# STM32F303RET6.net
KiCad netlist of a schematic drawn in Altium Designer
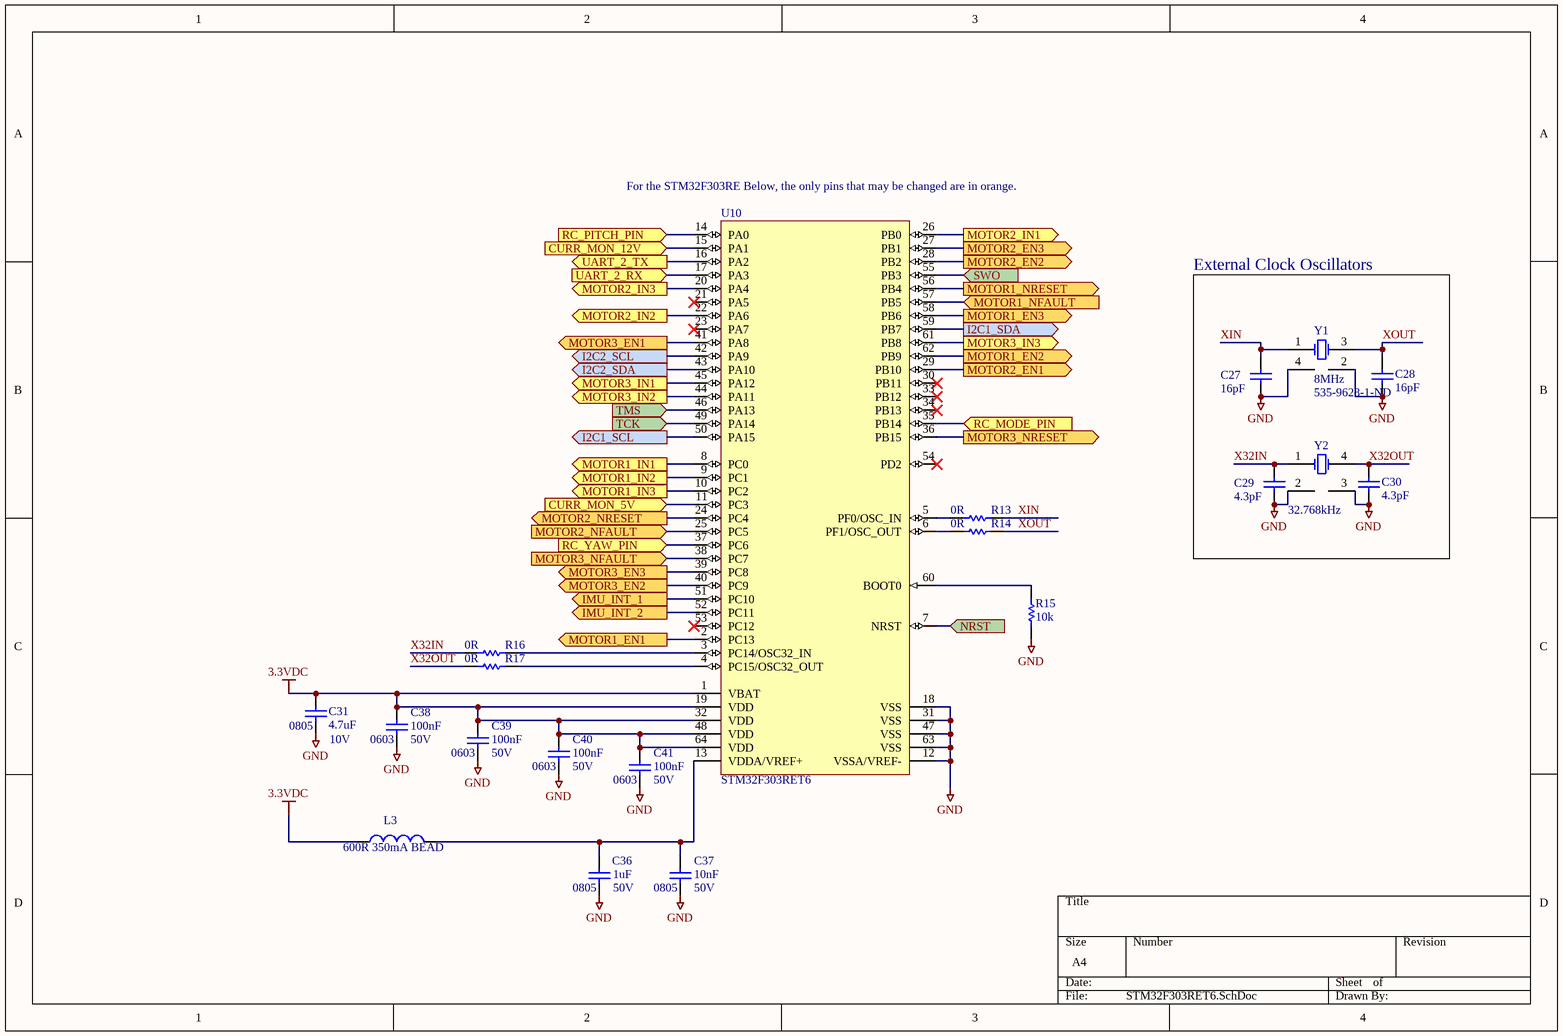
[diagram p0: STM32F303RET6.SchDoc]

(export (version "E")
  (design (tool "Eeschema 10.0.6"))
  (components
    (comp (ref "C27")
      (value "16pF")
      (footprint "CAPC1608N(0603\")")
      (description "Capacitor, Ceramic, 50V, +/- 5%, 0603, SMD, C0G/NP0")
      (fields
        (field (name "MFG") "Samsung Electro-Mechanics America, Inc")
        (field (name "VOLTAGE") "50V")
        (field (name "PUBLISHER") "UVic AERO, Luke Mills")
      )
      (libsource (lib "AERO Integrated Library - Capacitors") (part "16pF, 50V, 0603, SMD, Ceramic"))
    )
    (comp (ref "C28")
      (value "16pF")
      (footprint "CAPC1608N(0603\")")
      (description "Capacitor, Ceramic, 50V, +/- 5%, 0603, SMD, C0G/NP0")
      (fields
        (field (name "MFG") "Samsung Electro-Mechanics America, Inc")
        (field (name "VOLTAGE") "50V")
        (field (name "PUBLISHER") "UVic AERO, Luke Mills")
      )
      (libsource (lib "AERO Integrated Library - Capacitors") (part "16pF, 50V, 0603, SMD, Ceramic"))
    )
    (comp (ref "C29")
      (value "4.3pF")
      (footprint "CAPC1608N(0603\")")
      (description "Capacitor, Ceramic, 50V, +/- 0.1pF, 0603 SMD, C0G, NP0")
      (fields
        (field (name "MFG") "Samsung Electro-Mechanics")
        (field (name "PUBLISHER") "UVic AERO, Taylor Long")
      )
      (libsource (lib "AERO Integrated Library - Capacitors") (part "4.3pF 50V 0603 SMD, Ceramic"))
    )
    (comp (ref "C30")
      (value "4.3pF")
      (footprint "CAPC1608N(0603\")")
      (description "Capacitor, Ceramic, 50V, +/- 0.1pF, 0603 SMD, C0G, NP0")
      (fields
        (field (name "MFG") "Samsung Electro-Mechanics")
        (field (name "PUBLISHER") "UVic AERO, Taylor Long")
      )
      (libsource (lib "AERO Integrated Library - Capacitors") (part "4.3pF 50V 0603 SMD, Ceramic"))
    )
    (comp (ref "C31")
      (value "4.7uF")
      (footprint "CAPC2012N(0805\")")
      (description "CAP CER 4.7UF 10V, +/- 10%, 0805 SMD, X7R")
      (fields
        (field (name "MANUFACTURER") "KEMET")
        (field (name "MANUFACTURER PART NUMBER") "C0805C475K8PACTU")
        (field (name "CASE/PACKAGE") "0805")
        (field (name "VOLTAGE RATING (DC)") "10V")
        (field (name "PUBLISHER") "TRAXX Automation Ltd.")
      )
      (libsource (lib "BLDC_Gimbal_Lib") (part "C0805C475K8PACTU"))
    )
    (comp (ref "C36")
      (value "CL21A105KBCLNNC")
      (footprint "CAPC2012N(0805\")")
      (description "CAP CER 1uF 50V X5R 10% SMD 0805 85C Cardboard T/R")
      (fields
        (field (name "MANUFACTURER") "Samsung")
        (field (name "TOLERANCE") "10%")
        (field (name "VOLTAGE RATING") "50V")
        (field (name "CASE/PACKAGE") "0805")
        (field (name "CAPACITANCE") "1uF")
      )
      (libsource (lib "BLDC_Gimbal_Lib") (part "CL21A105KBCLNNC"))
    )
    (comp (ref "C37")
      (value "10nF")
      (footprint "CAPC2012N(0805\")")
      (description "CAP CER 10nF 50V, +/- 10%, 0805 SMD, X7R C0805C103K5RACTU")
      (fields
        (field (name "MANUFACTURER") "KEMET")
        (field (name "MANUFACTURER PART NUMBER") "C0805C103K5RACTU")
        (field (name "CASE/PACKAGE") "0805")
        (field (name "VOLTAGE RATING") "50V")
        (field (name "PUBLISHER") "UVic AERO")
      )
      (libsource (lib "BLDC_Gimbal_Lib") (part "C0805C103K5RACTU"))
    )
    (comp (ref "C38")
      (value "100nF")
      (footprint "CAPC1608N(0603\")")
      (description "CAP CER 0.1UF 50V X7R 0603")
      (fields
        (field (name "MANUFACTURER") "Samsung")
        (field (name "MANUFACTURER PART NUMBER") "CL10B104KB8SFNC")
        (field (name "CASE CODE (IMPERIAL)") "0603")
        (field (name "VOLTAGE RATING") "50V")
      )
      (libsource (lib "BLDC_Gimbal_Lib") (part "CL10B104KB8SFNC"))
    )
    (comp (ref "C39")
      (value "100nF")
      (footprint "CAPC1608N(0603\")")
      (description "CAP CER 0.1UF 50V X7R 0603")
      (fields
        (field (name "MANUFACTURER") "Samsung")
        (field (name "MANUFACTURER PART NUMBER") "CL10B104KB8SFNC")
        (field (name "CASE CODE (IMPERIAL)") "0603")
        (field (name "VOLTAGE RATING") "50V")
      )
      (libsource (lib "BLDC_Gimbal_Lib") (part "CL10B104KB8SFNC"))
    )
    (comp (ref "C40")
      (value "100nF")
      (footprint "CAPC1608N(0603\")")
      (description "CAP CER 0.1UF 50V X7R 0603")
      (fields
        (field (name "MANUFACTURER") "Samsung")
        (field (name "MANUFACTURER PART NUMBER") "CL10B104KB8SFNC")
        (field (name "CASE CODE (IMPERIAL)") "0603")
        (field (name "VOLTAGE RATING") "50V")
      )
      (libsource (lib "BLDC_Gimbal_Lib") (part "CL10B104KB8SFNC"))
    )
    (comp (ref "C41")
      (value "100nF")
      (footprint "CAPC1608N(0603\")")
      (description "CAP CER 0.1UF 50V X7R 0603")
      (fields
        (field (name "MANUFACTURER") "Samsung")
        (field (name "MANUFACTURER PART NUMBER") "CL10B104KB8SFNC")
        (field (name "CASE CODE (IMPERIAL)") "0603")
        (field (name "VOLTAGE RATING") "50V")
      )
      (libsource (lib "BLDC_Gimbal_Lib") (part "CL10B104KB8SFNC"))
    )
    (comp (ref "L3")
      (value "600R 350mA BEAD")
      (footprint "RESC1608N(0603\")")
      (description "FERRITE BEAD 600 OHM 0603 1LN")
      (fields
        (field (name "MANUFACTURER") "Taiyo Yuden")
        (field (name "MANUFACTURER PART NUMBER") "BK1608HS601-T")
      )
      (libsource (lib "BLDC_Gimbal_Lib") (part "BK1608HS601-T"))
    )
    (comp (ref "R13")
      (value "0R")
      (footprint "RESC1608N(0603\")")
      (description "Resistor, 0R, 1/10 W, 0603 SMD, 0R, +/-200ppm/C, Thick Film")
      (fields (field (name "POWER") "1/10W") (field (name "PUBLISHER") "TRAXX Automation Ltd."))
      (libsource (lib "BLDC_Gimbal_Lib") (part "0R, 1/10 W, 0603 SMD"))
    )
    (comp (ref "R14")
      (value "0R")
      (footprint "RESC1608N(0603\")")
      (description "Resistor, 0R, 1/10 W, 0603 SMD, 0R, +/-200ppm/C, Thick Film")
      (fields (field (name "POWER") "1/10W") (field (name "PUBLISHER") "TRAXX Automation Ltd."))
      (libsource (lib "BLDC_Gimbal_Lib") (part "0R, 1/10 W, 0603 SMD"))
    )
    (comp (ref "R15")
      (value "CRCW080510K0FKEA")
      (footprint "RESC2012N(0805\")")
      (description "RES SMD 10K OHM 1% 1/8W 0805")
      (fields
        (field (name "MANUFACTURER") "Vishay")
        (field (name "TOLERANCE") "1%")
        (field (name "RESISTANCE") "10k")
      )
      (libsource (lib "BLDC_Gimbal_Lib") (part "CRCW080510K0FKEA"))
    )
    (comp (ref "R16")
      (value "0R")
      (footprint "RESC1608N(0603\")")
      (description "Resistor, 0R, 1/10 W, 0603 SMD, 0R, +/-200ppm/C, Thick Film")
      (fields (field (name "POWER") "1/10W") (field (name "PUBLISHER") "TRAXX Automation Ltd."))
      (libsource (lib "BLDC_Gimbal_Lib") (part "0R, 1/10 W, 0603 SMD"))
    )
    (comp (ref "R17")
      (value "0R")
      (footprint "RESC1608N(0603\")")
      (description "Resistor, 0R, 1/10 W, 0603 SMD, 0R, +/-200ppm/C, Thick Film")
      (fields (field (name "POWER") "1/10W") (field (name "PUBLISHER") "TRAXX Automation Ltd."))
      (libsource (lib "BLDC_Gimbal_Lib") (part "0R, 1/10 W, 0603 SMD"))
    )
    (comp (ref "U10")
      (value "STM32F303RET6")
      (footprint "STM-LQFP64_M")
      (libsource (lib "BLDC_Gimbal_Lib") (part "CMP-0537-00048-1"))
    )
    (comp (ref "Y1")
      (value "8MHz")
      (footprint "CRYSTAL 4-SMD, 3.60x6.00mm")
      (description "Crystal Oscillator 8MHz, 18pF, 4-SMD")
      (fields
        (field (name "SUPPLIER PART NUMBER 1") "535-9628-1-ND")
        (field (name "PUBLISHER") "UVic AERO, Taylor Long")
      )
      (libsource (lib "AERO Schematic Library - Crystals & Oscillators") (part "Crystal 8MHz, 18pF, 4-SMD 6.0x3.6mm"))
    )
    (comp (ref "Y2")
      (value "32.768kHz")
      (footprint "SOJ550P380X260-4M")
      (description "Crystal Oscillator 32.768kHz, 4-SOJ 5.5mm")
      (fields (field (name "PUBLISHER") "UVic AERO. Taylor Long"))
      (libsource (lib "AERO Schematic Library - Crystals & Oscillators") (part "Crystal 32.768khz, 4-SOJ 5.5mm"))
    )
  )
  (nets
    (net (code "1") (name "/CURR_MON_5V") (class "Default")
      (node (ref "U10") (pin "11") (pinfunction "PC3_11") (pintype "bidirectional"))
    )
    (net (code "2") (name "/CURR_MON_12V") (class "Default")
      (node (ref "U10") (pin "15") (pinfunction "PA1_15") (pintype "bidirectional"))
    )
    (net (code "3") (name "/I2C1_SCL") (class "Default")
      (node (ref "U10") (pin "50") (pinfunction "PA15_50") (pintype "bidirectional"))
    )
    (net (code "4") (name "/I2C1_SDA") (class "Default")
      (node (ref "U10") (pin "59") (pinfunction "PB7_59") (pintype "bidirectional"))
    )
    (net (code "5") (name "/I2C2_SCL") (class "Default")
      (node (ref "U10") (pin "42") (pinfunction "PA9_42") (pintype "bidirectional"))
    )
    (net (code "6") (name "/I2C2_SDA") (class "Default")
      (node (ref "U10") (pin "43") (pinfunction "PA10_43") (pintype "bidirectional"))
    )
    (net (code "7") (name "/IMU_INT_1") (class "Default")
      (node (ref "U10") (pin "51") (pinfunction "PC10_51") (pintype "bidirectional"))
    )
    (net (code "8") (name "/IMU_INT_2") (class "Default")
      (node (ref "U10") (pin "52") (pinfunction "PC11_52") (pintype "bidirectional"))
    )
    (net (code "9") (name "/MOTOR1_EN1") (class "Default")
      (node (ref "U10") (pin "2") (pinfunction "PC13_2") (pintype "bidirectional"))
    )
    (net (code "10") (name "/MOTOR1_EN2") (class "Default")
      (node (ref "U10") (pin "62") (pinfunction "PB9_62") (pintype "bidirectional"))
    )
    (net (code "11") (name "/MOTOR1_EN3") (class "Default")
      (node (ref "U10") (pin "58") (pinfunction "PB6_58") (pintype "bidirectional"))
    )
    (net (code "12") (name "/MOTOR1_IN1") (class "Default")
      (node (ref "U10") (pin "8") (pinfunction "PC0_8") (pintype "bidirectional"))
    )
    (net (code "13") (name "/MOTOR1_IN2") (class "Default")
      (node (ref "U10") (pin "9") (pinfunction "PC1_9") (pintype "bidirectional"))
    )
    (net (code "14") (name "/MOTOR1_IN3") (class "Default")
      (node (ref "U10") (pin "10") (pinfunction "PC2_10") (pintype "bidirectional"))
    )
    (net (code "15") (name "/MOTOR1_NFAULT") (class "Default")
      (node (ref "U10") (pin "57") (pinfunction "PB5_57") (pintype "bidirectional"))
    )
    (net (code "16") (name "/MOTOR1_NRESET") (class "Default")
      (node (ref "U10") (pin "56") (pinfunction "PB4_56") (pintype "bidirectional"))
    )
    (net (code "17") (name "/MOTOR2_EN1") (class "Default")
      (node (ref "U10") (pin "29") (pinfunction "PB10_29") (pintype "bidirectional"))
    )
    (net (code "18") (name "/MOTOR2_EN2") (class "Default")
      (node (ref "U10") (pin "28") (pinfunction "PB2_28") (pintype "bidirectional"))
    )
    (net (code "19") (name "/MOTOR2_EN3") (class "Default")
      (node (ref "U10") (pin "27") (pinfunction "PB1_27") (pintype "bidirectional"))
    )
    (net (code "20") (name "/MOTOR2_IN1") (class "Default")
      (node (ref "U10") (pin "26") (pinfunction "PB0_26") (pintype "bidirectional"))
    )
    (net (code "21") (name "/MOTOR2_IN2") (class "Default")
      (node (ref "U10") (pin "22") (pinfunction "PA6_22") (pintype "bidirectional"))
    )
    (net (code "22") (name "/MOTOR2_IN3") (class "Default")
      (node (ref "U10") (pin "20") (pinfunction "PA4_20") (pintype "bidirectional"))
    )
    (net (code "23") (name "/MOTOR2_NFAULT") (class "Default")
      (node (ref "U10") (pin "25") (pinfunction "PC5_25") (pintype "bidirectional"))
    )
    (net (code "24") (name "/MOTOR2_NRESET") (class "Default")
      (node (ref "U10") (pin "24") (pinfunction "PC4_24") (pintype "bidirectional"))
    )
    (net (code "25") (name "/MOTOR3_EN1") (class "Default")
      (node (ref "U10") (pin "41") (pinfunction "PA8_41") (pintype "bidirectional"))
    )
    (net (code "26") (name "/MOTOR3_EN2") (class "Default")
      (node (ref "U10") (pin "40") (pinfunction "PC9_40") (pintype "bidirectional"))
    )
    (net (code "27") (name "/MOTOR3_EN3") (class "Default")
      (node (ref "U10") (pin "39") (pinfunction "PC8_39") (pintype "bidirectional"))
    )
    (net (code "28") (name "/MOTOR3_IN1") (class "Default")
      (node (ref "U10") (pin "45") (pinfunction "PA12_45") (pintype "bidirectional"))
    )
    (net (code "29") (name "/MOTOR3_IN2") (class "Default")
      (node (ref "U10") (pin "44") (pinfunction "PA11_44") (pintype "bidirectional"))
    )
    (net (code "30") (name "/MOTOR3_IN3") (class "Default")
      (node (ref "U10") (pin "61") (pinfunction "PB8_61") (pintype "bidirectional"))
    )
    (net (code "31") (name "/MOTOR3_NFAULT") (class "Default")
      (node (ref "U10") (pin "38") (pinfunction "PC7_38") (pintype "bidirectional"))
    )
    (net (code "32") (name "/MOTOR3_NRESET") (class "Default")
      (node (ref "U10") (pin "36") (pinfunction "PB15_36") (pintype "bidirectional"))
    )
    (net (code "33") (name "/NRST") (class "Default")
      (node (ref "U10") (pin "7") (pinfunction "NRST_7") (pintype "bidirectional"))
    )
    (net (code "34") (name "/RC_MODE_PIN") (class "Default")
      (node (ref "U10") (pin "35") (pinfunction "PB14_35") (pintype "bidirectional"))
    )
    (net (code "35") (name "/RC_PITCH_PIN") (class "Default")
      (node (ref "U10") (pin "14") (pinfunction "PA0_14") (pintype "bidirectional"))
    )
    (net (code "36") (name "/RC_YAW_PIN") (class "Default")
      (node (ref "U10") (pin "37") (pinfunction "PC6_37") (pintype "bidirectional"))
    )
    (net (code "37") (name "/SWO") (class "Default")
      (node (ref "U10") (pin "55") (pinfunction "PB3_55") (pintype "bidirectional"))
    )
    (net (code "38") (name "/TCK") (class "Default")
      (node (ref "U10") (pin "49") (pinfunction "PA14_49") (pintype "bidirectional"))
    )
    (net (code "39") (name "/TMS") (class "Default")
      (node (ref "U10") (pin "46") (pinfunction "PA13_46") (pintype "bidirectional"))
    )
    (net (code "40") (name "/UART_2_RX") (class "Default")
      (node (ref "U10") (pin "17") (pinfunction "PA3_17") (pintype "bidirectional"))
    )
    (net (code "41") (name "/UART_2_TX") (class "Default")
      (node (ref "U10") (pin "16") (pinfunction "PA2_16") (pintype "bidirectional"))
    )
    (net (code "42") (name "/X32IN") (class "Default")
      (node (ref "C29") (pin "2") (pinfunction "2_2") (pintype "passive"))
      (node (ref "R16") (pin "1") (pinfunction "1_1") (pintype "passive"))
      (node (ref "Y2") (pin "1") (pinfunction "OSC1_1") (pintype "passive"))
    )
    (net (code "43") (name "/X32OUT") (class "Default")
      (node (ref "C30") (pin "2") (pinfunction "2_2") (pintype "passive"))
      (node (ref "R17") (pin "1") (pinfunction "1_1") (pintype "passive"))
      (node (ref "Y2") (pin "4") (pinfunction "OSC2_4") (pintype "passive"))
    )
    (net (code "44") (name "/XIN") (class "Default")
      (node (ref "C27") (pin "2") (pinfunction "2_2") (pintype "passive"))
      (node (ref "R13") (pin "2") (pinfunction "2_2") (pintype "passive"))
      (node (ref "Y1") (pin "1") (pinfunction "OSC1_1") (pintype "passive"))
    )
    (net (code "45") (name "/XOUT") (class "Default")
      (node (ref "C28") (pin "2") (pinfunction "2_2") (pintype "passive"))
      (node (ref "R14") (pin "2") (pinfunction "2_2") (pintype "passive"))
      (node (ref "Y1") (pin "3") (pinfunction "OSC2_3") (pintype "passive"))
    )
    (net (code "46") (name "3.3VDC") (class "Default")
      (node (ref "C31") (pin "2") (pinfunction "2_2") (pintype "passive"))
      (node (ref "C38") (pin "2") (pinfunction "2_2") (pintype "passive"))
      (node (ref "C39") (pin "2") (pinfunction "2_2") (pintype "passive"))
      (node (ref "C40") (pin "2") (pinfunction "2_2") (pintype "passive"))
      (node (ref "C41") (pin "2") (pinfunction "2_2") (pintype "passive"))
      (node (ref "L3") (pin "1") (pinfunction "1_1") (pintype "passive"))
      (node (ref "U10") (pin "1") (pinfunction "VBAT_1") (pintype "power_in"))
      (node (ref "U10") (pin "19") (pinfunction "VDD_19") (pintype "power_in"))
      (node (ref "U10") (pin "32") (pinfunction "VDD_32") (pintype "power_in"))
      (node (ref "U10") (pin "48") (pinfunction "VDD_48") (pintype "power_in"))
      (node (ref "U10") (pin "64") (pinfunction "VDD_64") (pintype "power_in"))
    )
    (net (code "47") (name "GND") (class "Default")
      (node (ref "C27") (pin "1") (pinfunction "1_1") (pintype "passive"))
      (node (ref "C28") (pin "1") (pinfunction "1_1") (pintype "passive"))
      (node (ref "C29") (pin "1") (pinfunction "1_1") (pintype "passive"))
      (node (ref "C30") (pin "1") (pinfunction "1_1") (pintype "passive"))
      (node (ref "C31") (pin "1") (pinfunction "1_1") (pintype "passive"))
      (node (ref "C36") (pin "1") (pinfunction "1_1") (pintype "passive"))
      (node (ref "C37") (pin "1") (pinfunction "1_1") (pintype "passive"))
      (node (ref "C38") (pin "1") (pinfunction "1_1") (pintype "passive"))
      (node (ref "C39") (pin "1") (pinfunction "1_1") (pintype "passive"))
      (node (ref "C40") (pin "1") (pinfunction "1_1") (pintype "passive"))
      (node (ref "C41") (pin "1") (pinfunction "1_1") (pintype "passive"))
      (node (ref "R15") (pin "1") (pinfunction "1_1") (pintype "passive"))
      (node (ref "U10") (pin "12") (pinfunction "VSSA/VREF-_12") (pintype "power_in"))
      (node (ref "U10") (pin "18") (pinfunction "VSS_18") (pintype "power_in"))
      (node (ref "U10") (pin "31") (pinfunction "VSS_31") (pintype "power_in"))
      (node (ref "U10") (pin "47") (pinfunction "VSS_47") (pintype "power_in"))
      (node (ref "U10") (pin "63") (pinfunction "VSS_63") (pintype "power_in"))
      (node (ref "Y1") (pin "2") (pinfunction "OSC1_2") (pintype "passive"))
      (node (ref "Y1") (pin "4") (pinfunction "OSC1_4") (pintype "passive"))
      (node (ref "Y2") (pin "2") (pinfunction "GND_2") (pintype "passive"))
      (node (ref "Y2") (pin "3") (pinfunction "GND_3") (pintype "passive"))
    )
    (net (code "48") (name "Net-(U10-BOOT0)") (class "Default")
      (node (ref "R15") (pin "2") (pinfunction "2_2") (pintype "passive"))
      (node (ref "U10") (pin "60") (pinfunction "BOOT0_60") (pintype "input"))
    )
    (net (code "49") (name "Net-(U10-PC14{slash}OSC32_IN)") (class "Default")
      (node (ref "R16") (pin "2") (pinfunction "2_2") (pintype "passive"))
      (node (ref "U10") (pin "3") (pinfunction "PC14/OSC32_IN_3") (pintype "bidirectional"))
    )
    (net (code "50") (name "Net-(U10-PC15{slash}OSC32_OUT)") (class "Default")
      (node (ref "R17") (pin "2") (pinfunction "2_2") (pintype "passive"))
      (node (ref "U10") (pin "4") (pinfunction "PC15/OSC32_OUT_4") (pintype "bidirectional"))
    )
    (net (code "51") (name "Net-(U10-PF0{slash}OSC_IN)") (class "Default")
      (node (ref "R13") (pin "1") (pinfunction "1_1") (pintype "passive"))
      (node (ref "U10") (pin "5") (pinfunction "PF0/OSC_IN_5") (pintype "bidirectional"))
    )
    (net (code "52") (name "Net-(U10-PF1{slash}OSC_OUT)") (class "Default")
      (node (ref "R14") (pin "1") (pinfunction "1_1") (pintype "passive"))
      (node (ref "U10") (pin "6") (pinfunction "PF1/OSC_OUT_6") (pintype "bidirectional"))
    )
    (net (code "53") (name "Net-(U10-VDDA{slash}VREF+)") (class "Default")
      (node (ref "C36") (pin "2") (pinfunction "2_2") (pintype "passive"))
      (node (ref "C37") (pin "2") (pinfunction "2_2") (pintype "passive"))
      (node (ref "L3") (pin "2") (pinfunction "2_2") (pintype "passive"))
      (node (ref "U10") (pin "13") (pinfunction "VDDA/VREF+_13") (pintype "power_in"))
    )
    (net (code "54") (name "unconnected-(U10-PA5-Pad21)") (class "Default")
      (node (ref "U10") (pin "21") (pinfunction "PA5_21") (pintype "bidirectional+no_connect"))
    )
    (net (code "55") (name "unconnected-(U10-PA7-Pad23)") (class "Default")
      (node (ref "U10") (pin "23") (pinfunction "PA7_23") (pintype "bidirectional+no_connect"))
    )
    (net (code "56") (name "unconnected-(U10-PB11-Pad30)") (class "Default")
      (node (ref "U10") (pin "30") (pinfunction "PB11_30") (pintype "bidirectional+no_connect"))
    )
    (net (code "57") (name "unconnected-(U10-PB12-Pad33)") (class "Default")
      (node (ref "U10") (pin "33") (pinfunction "PB12_33") (pintype "bidirectional+no_connect"))
    )
    (net (code "58") (name "unconnected-(U10-PB13-Pad34)") (class "Default")
      (node (ref "U10") (pin "34") (pinfunction "PB13_34") (pintype "bidirectional+no_connect"))
    )
    (net (code "59") (name "unconnected-(U10-PC12-Pad53)") (class "Default")
      (node (ref "U10") (pin "53") (pinfunction "PC12_53") (pintype "bidirectional+no_connect"))
    )
    (net (code "60") (name "unconnected-(U10-PD2-Pad54)") (class "Default")
      (node (ref "U10") (pin "54") (pinfunction "PD2_54") (pintype "bidirectional+no_connect"))
    )
  )
)
